# CUK_3Ph_Analog_Isolation.net
KiCad netlist of a schematic drawn in Altium Designer
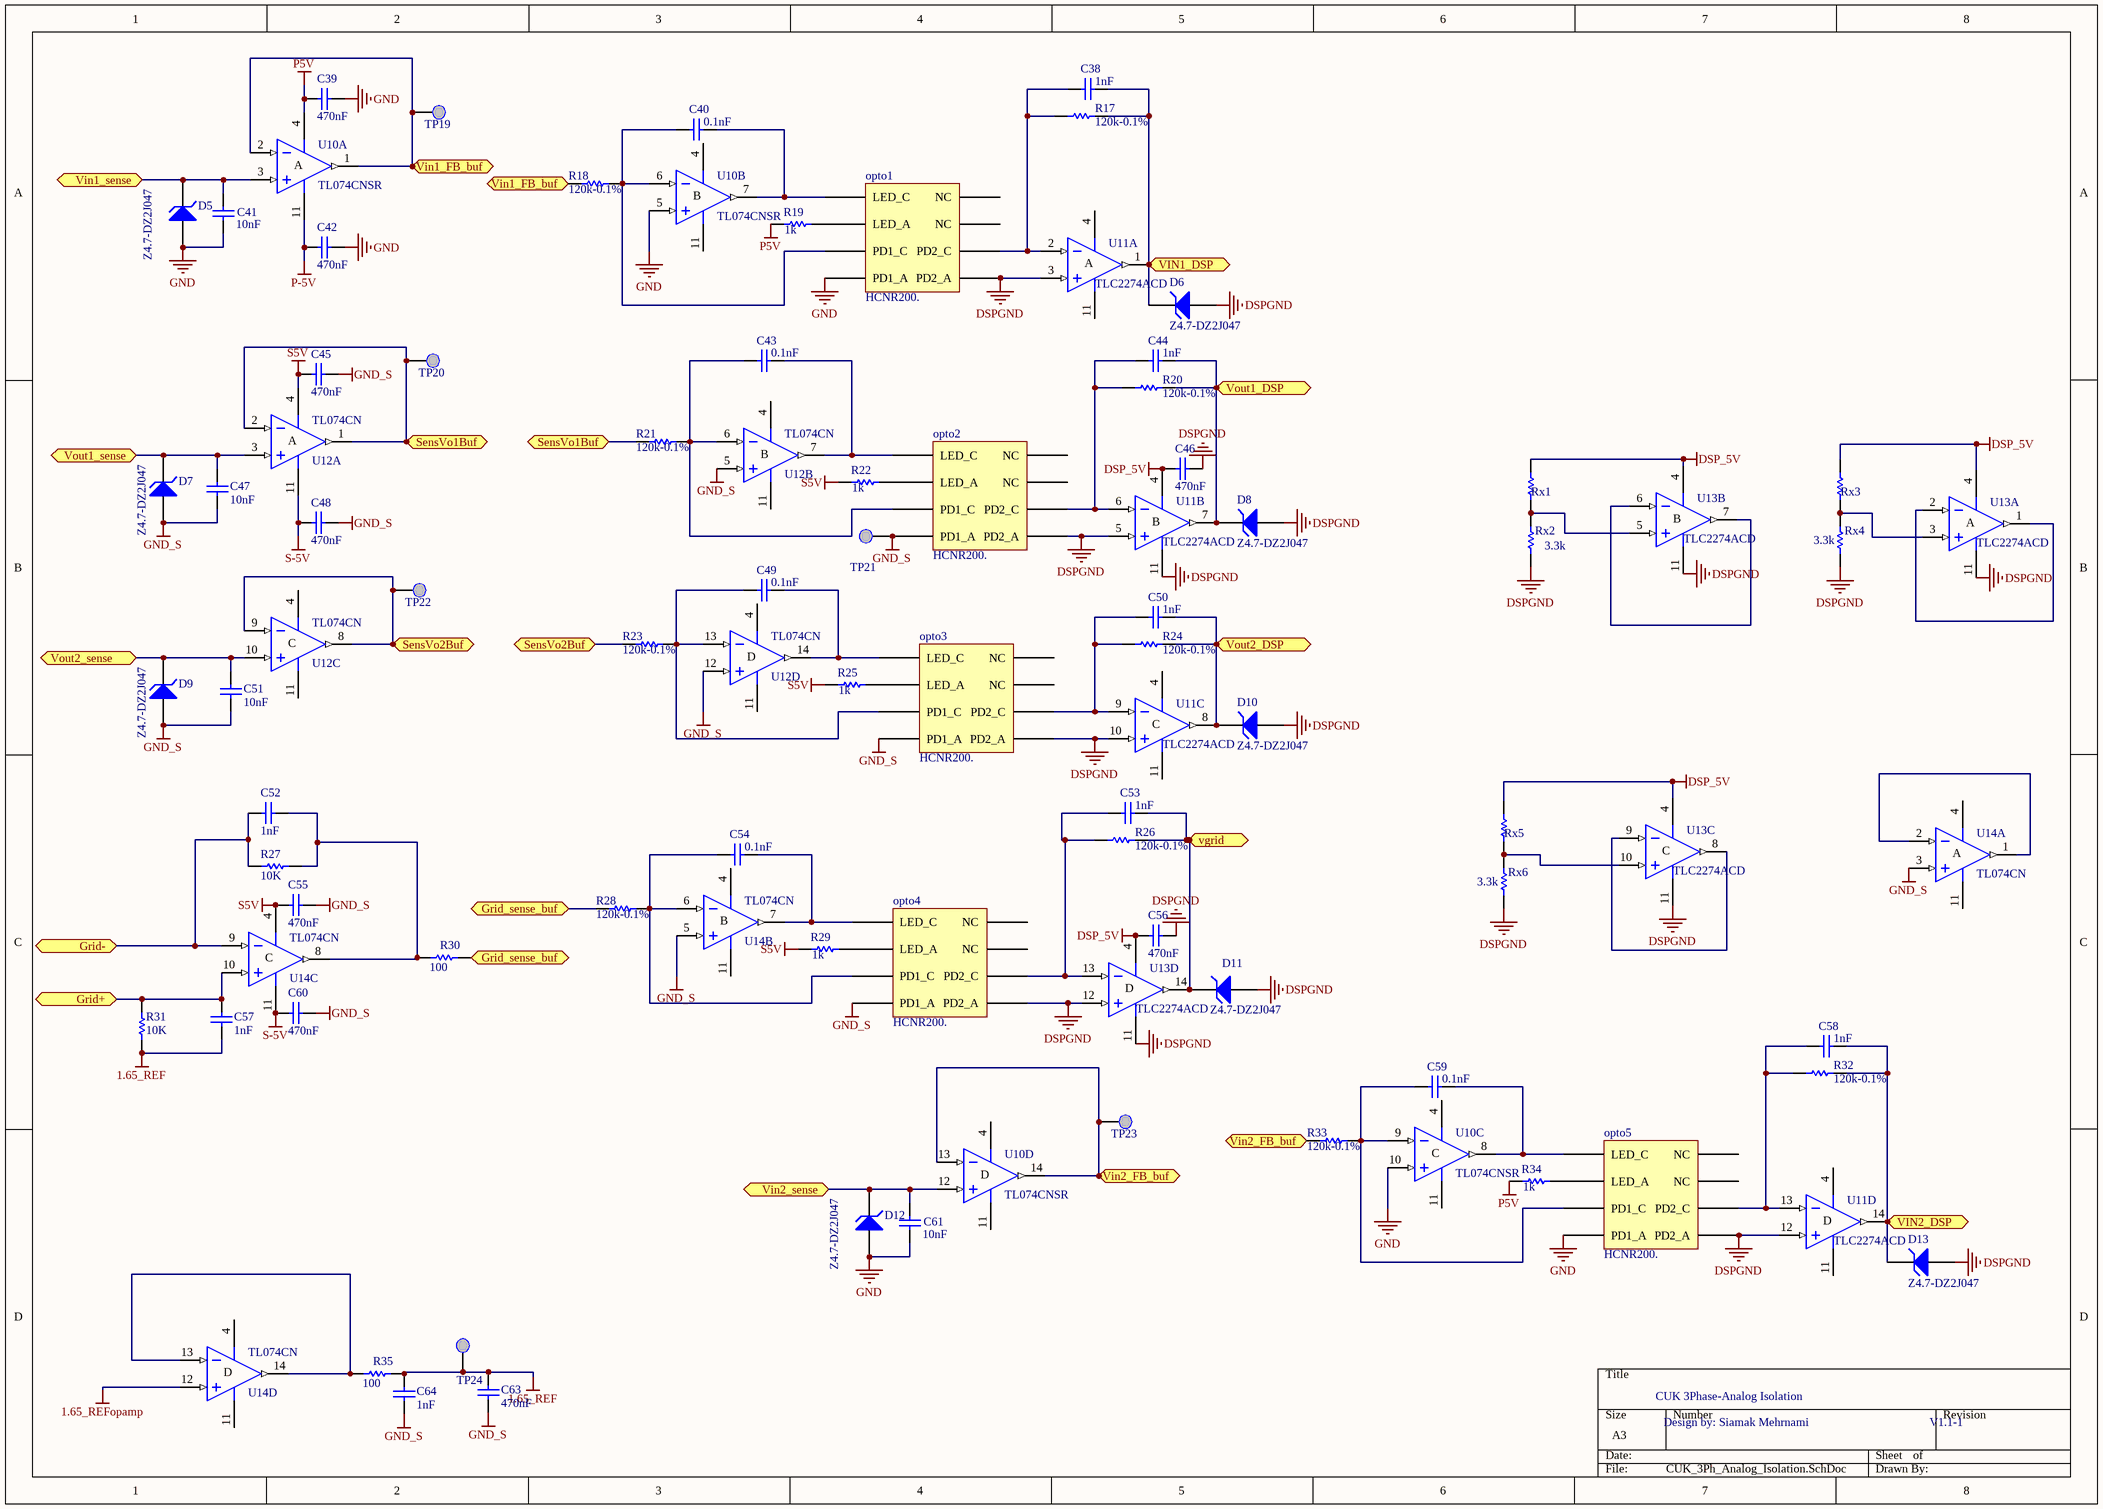
[diagram p0: CUK_3Ph_Analog_Isolation.SchDoc]

(export (version "E")
  (design (tool "Eeschema 10.0.6"))
  (components
    (comp (ref "C38")
      (value "1nF")
      (footprint "Capacitor 0805")
      (description "Capacitor")
      (fields (field (name "Comment") "Cap") (field (name "PUBLISHER") "Altium Limited"))
      (libsource (lib "Miscellaneous Devices") (part "Cap"))
    )
    (comp (ref "C39")
      (value "470nF")
      (footprint "Capacitor 0805")
      (description "Capacitor")
      (fields (field (name "Comment") "Cap") (field (name "PUBLISHER") "Altium Limited"))
      (libsource (lib "Miscellaneous Devices") (part "Cap"))
    )
    (comp (ref "C40")
      (value "0.1nF")
      (footprint "Capacitor 0805")
      (description "Capacitor")
      (fields (field (name "Comment") "Cap") (field (name "PUBLISHER") "Altium Limited"))
      (libsource (lib "Miscellaneous Devices") (part "Cap"))
    )
    (comp (ref "C41")
      (value "10nF")
      (footprint "Capacitor 0805")
      (description "Capacitor")
      (fields (field (name "Comment") "Cap") (field (name "PUBLISHER") "Altium Limited"))
      (libsource (lib "Miscellaneous Devices") (part "Cap"))
    )
    (comp (ref "C42")
      (value "470nF")
      (footprint "Capacitor 0805")
      (description "Capacitor")
      (fields (field (name "Comment") "Cap") (field (name "PUBLISHER") "Altium Limited"))
      (libsource (lib "Miscellaneous Devices") (part "Cap"))
    )
    (comp (ref "C43")
      (value "0.1nF")
      (footprint "Capacitor 0805")
      (description "Capacitor")
      (fields (field (name "Comment") "Cap") (field (name "PUBLISHER") "Altium Limited"))
      (libsource (lib "Miscellaneous Devices") (part "Cap"))
    )
    (comp (ref "C44")
      (value "1nF")
      (footprint "Capacitor 0805")
      (description "Capacitor")
      (fields (field (name "Comment") "Cap") (field (name "PUBLISHER") "Altium Limited"))
      (libsource (lib "Miscellaneous Devices") (part "Cap"))
    )
    (comp (ref "C45")
      (value "470nF")
      (footprint "Capacitor 0805")
      (description "Capacitor")
      (fields (field (name "Comment") "Cap") (field (name "PUBLISHER") "Altium Limited"))
      (libsource (lib "Miscellaneous Devices") (part "Cap"))
    )
    (comp (ref "C46")
      (value "470nF")
      (footprint "Capacitor 0805")
      (description "Capacitor")
      (fields (field (name "Comment") "Cap") (field (name "PUBLISHER") "Altium Limited"))
      (libsource (lib "Miscellaneous Devices") (part "Cap"))
    )
    (comp (ref "C47")
      (value "10nF")
      (footprint "Capacitor 0805")
      (description "Capacitor")
      (fields (field (name "Comment") "Cap") (field (name "PUBLISHER") "Altium Limited"))
      (libsource (lib "Miscellaneous Devices") (part "Cap"))
    )
    (comp (ref "C48")
      (value "470nF")
      (footprint "Capacitor 0805")
      (description "Capacitor")
      (fields (field (name "Comment") "Cap") (field (name "PUBLISHER") "Altium Limited"))
      (libsource (lib "Miscellaneous Devices") (part "Cap"))
    )
    (comp (ref "C49")
      (value "0.1nF")
      (footprint "Capacitor 0805")
      (description "Capacitor")
      (fields (field (name "Comment") "Cap") (field (name "PUBLISHER") "Altium Limited"))
      (libsource (lib "Miscellaneous Devices") (part "Cap"))
    )
    (comp (ref "C50")
      (value "1nF")
      (footprint "Capacitor 0805")
      (description "Capacitor")
      (fields (field (name "Comment") "Cap") (field (name "PUBLISHER") "Altium Limited"))
      (libsource (lib "Miscellaneous Devices") (part "Cap"))
    )
    (comp (ref "C51")
      (value "10nF")
      (footprint "Capacitor 0805")
      (description "Capacitor")
      (fields (field (name "Comment") "Cap") (field (name "PUBLISHER") "Altium Limited"))
      (libsource (lib "Miscellaneous Devices") (part "Cap"))
    )
    (comp (ref "C52")
      (value "1nF")
      (footprint "Capacitor 0805")
      (description "Capacitor")
      (fields (field (name "Comment") "Cap") (field (name "PUBLISHER") "Altium Limited"))
      (libsource (lib "Miscellaneous Devices") (part "Cap"))
    )
    (comp (ref "C53")
      (value "1nF")
      (footprint "Capacitor 0805")
      (description "Capacitor")
      (fields (field (name "Comment") "Cap") (field (name "PUBLISHER") "Altium Limited"))
      (libsource (lib "Miscellaneous Devices") (part "Cap"))
    )
    (comp (ref "C54")
      (value "0.1nF")
      (footprint "Capacitor 0805")
      (description "Capacitor")
      (fields (field (name "Comment") "Cap") (field (name "PUBLISHER") "Altium Limited"))
      (libsource (lib "Miscellaneous Devices") (part "Cap"))
    )
    (comp (ref "C55")
      (value "470nF")
      (footprint "Capacitor 0805")
      (description "Capacitor")
      (fields (field (name "Comment") "Cap") (field (name "PUBLISHER") "Altium Limited"))
      (libsource (lib "Miscellaneous Devices") (part "Cap"))
    )
    (comp (ref "C56")
      (value "470nF")
      (footprint "Capacitor 0805")
      (description "Capacitor")
      (fields (field (name "Comment") "Cap") (field (name "PUBLISHER") "Altium Limited"))
      (libsource (lib "Miscellaneous Devices") (part "Cap"))
    )
    (comp (ref "C57")
      (value "1nF")
      (footprint "Capacitor 0805")
      (description "Capacitor")
      (fields (field (name "Comment") "Cap") (field (name "PUBLISHER") "Altium Limited"))
      (libsource (lib "Miscellaneous Devices") (part "Cap"))
    )
    (comp (ref "C58")
      (value "1nF")
      (footprint "Capacitor 0805")
      (description "Capacitor")
      (fields (field (name "Comment") "Cap") (field (name "PUBLISHER") "Altium Limited"))
      (libsource (lib "Miscellaneous Devices") (part "Cap"))
    )
    (comp (ref "C59")
      (value "0.1nF")
      (footprint "Capacitor 0805")
      (description "Capacitor")
      (fields (field (name "Comment") "Cap") (field (name "PUBLISHER") "Altium Limited"))
      (libsource (lib "Miscellaneous Devices") (part "Cap"))
    )
    (comp (ref "C60")
      (value "470nF")
      (footprint "Capacitor 0805")
      (description "Capacitor")
      (fields (field (name "Comment") "Cap") (field (name "PUBLISHER") "Altium Limited"))
      (libsource (lib "Miscellaneous Devices") (part "Cap"))
    )
    (comp (ref "C61")
      (value "10nF")
      (footprint "Capacitor 0805")
      (description "Capacitor")
      (fields (field (name "Comment") "Cap") (field (name "PUBLISHER") "Altium Limited"))
      (libsource (lib "Miscellaneous Devices") (part "Cap"))
    )
    (comp (ref "C63")
      (value "470nF")
      (footprint "Capacitor 0805")
      (description "Capacitor")
      (fields (field (name "Comment") "Cap") (field (name "PUBLISHER") "Altium Limited"))
      (libsource (lib "Miscellaneous Devices") (part "Cap"))
    )
    (comp (ref "C64")
      (value "1nF")
      (footprint "Capacitor 0805")
      (description "Capacitor")
      (fields (field (name "Comment") "Cap") (field (name "PUBLISHER") "Altium Limited"))
      (libsource (lib "Miscellaneous Devices") (part "Cap"))
    )
    (comp (ref "D5")
      (value "Z4.7-DZ2J047")
      (footprint "Zener DZ2J047")
      (description "Zener Diode")
      (fields (field (name "PUBLISHER") "Altium Limited"))
      (libsource (lib "Miscellaneous Devices") (part "D Zener"))
    )
    (comp (ref "D6")
      (value "Z4.7-DZ2J047")
      (footprint "Zener DZ2J047")
      (description "Zener Diode")
      (fields (field (name "PUBLISHER") "Altium Limited"))
      (libsource (lib "Miscellaneous Devices") (part "D Zener"))
    )
    (comp (ref "D7")
      (value "Z4.7-DZ2J047")
      (footprint "Zener DZ2J047")
      (description "Zener Diode")
      (fields (field (name "PUBLISHER") "Altium Limited"))
      (libsource (lib "Miscellaneous Devices") (part "D Zener"))
    )
    (comp (ref "D8")
      (value "Z4.7-DZ2J047")
      (footprint "Zener DZ2J047")
      (description "Zener Diode")
      (fields (field (name "PUBLISHER") "Altium Limited"))
      (libsource (lib "Miscellaneous Devices") (part "D Zener"))
    )
    (comp (ref "D9")
      (value "Z4.7-DZ2J047")
      (footprint "Zener DZ2J047")
      (description "Zener Diode")
      (fields (field (name "PUBLISHER") "Altium Limited"))
      (libsource (lib "Miscellaneous Devices") (part "D Zener"))
    )
    (comp (ref "D10")
      (value "Z4.7-DZ2J047")
      (footprint "Zener DZ2J047")
      (description "Zener Diode")
      (fields (field (name "PUBLISHER") "Altium Limited"))
      (libsource (lib "Miscellaneous Devices") (part "D Zener"))
    )
    (comp (ref "D11")
      (value "Z4.7-DZ2J047")
      (footprint "Zener DZ2J047")
      (description "Zener Diode")
      (fields (field (name "PUBLISHER") "Altium Limited"))
      (libsource (lib "Miscellaneous Devices") (part "D Zener"))
    )
    (comp (ref "D12")
      (value "Z4.7-DZ2J047")
      (footprint "Zener DZ2J047")
      (description "Zener Diode")
      (fields (field (name "PUBLISHER") "Altium Limited"))
      (libsource (lib "Miscellaneous Devices") (part "D Zener"))
    )
    (comp (ref "D13")
      (value "Z4.7-DZ2J047")
      (footprint "Zener DZ2J047")
      (description "Zener Diode")
      (fields (field (name "PUBLISHER") "Altium Limited"))
      (libsource (lib "Miscellaneous Devices") (part "D Zener"))
    )
    (comp (ref "opto1")
      (value "HCNR200.")
      (footprint "HCNR200")
      (libsource (lib "HCRN200") (part "Component_1"))
    )
    (comp (ref "opto2")
      (value "HCNR200.")
      (footprint "HCNR200")
      (libsource (lib "HCRN200") (part "Component_1"))
    )
    (comp (ref "opto3")
      (value "HCNR200.")
      (footprint "HCNR200")
      (libsource (lib "HCRN200") (part "Component_1"))
    )
    (comp (ref "opto4")
      (value "HCNR200.")
      (footprint "HCNR200")
      (libsource (lib "HCRN200") (part "Component_1"))
    )
    (comp (ref "opto5")
      (value "HCNR200.")
      (footprint "HCNR200")
      (libsource (lib "HCRN200") (part "Component_1"))
    )
    (comp (ref "R17")
      (value "120k-0.1%")
      (footprint "0805 RES")
      (description "Resistor")
      (fields (field (name "Comment") "Res1") (field (name "PUBLISHER") "Altium Limited"))
      (libsource (lib "Miscellaneous Devices") (part "Res1"))
    )
    (comp (ref "R18")
      (value "120k-0.1%")
      (footprint "0805 RES")
      (description "Resistor")
      (fields (field (name "Comment") "Res1") (field (name "PUBLISHER") "Altium Limited"))
      (libsource (lib "Miscellaneous Devices") (part "Res1"))
    )
    (comp (ref "R19")
      (value "1k")
      (footprint "0805 RES")
      (description "Resistor")
      (fields (field (name "Comment") "Res1") (field (name "PUBLISHER") "Altium Limited"))
      (libsource (lib "Miscellaneous Devices") (part "Res1"))
    )
    (comp (ref "R20")
      (value "120k-0.1%")
      (footprint "0805 RES")
      (description "Resistor")
      (fields (field (name "Comment") "Res1") (field (name "PUBLISHER") "Altium Limited"))
      (libsource (lib "Miscellaneous Devices") (part "Res1"))
    )
    (comp (ref "R21")
      (value "120k-0.1%")
      (footprint "0805 RES")
      (description "Resistor")
      (fields (field (name "Comment") "Res1") (field (name "PUBLISHER") "Altium Limited"))
      (libsource (lib "Miscellaneous Devices") (part "Res1"))
    )
    (comp (ref "R22")
      (value "1k")
      (footprint "0805 RES")
      (description "Resistor")
      (fields (field (name "Comment") "Res1") (field (name "PUBLISHER") "Altium Limited"))
      (libsource (lib "Miscellaneous Devices") (part "Res1"))
    )
    (comp (ref "R23")
      (value "120k-0.1%")
      (footprint "0805 RES")
      (description "Resistor")
      (fields (field (name "Comment") "Res1") (field (name "PUBLISHER") "Altium Limited"))
      (libsource (lib "Miscellaneous Devices") (part "Res1"))
    )
    (comp (ref "R24")
      (value "120k-0.1%")
      (footprint "0805 RES")
      (description "Resistor")
      (fields (field (name "Comment") "Res1") (field (name "PUBLISHER") "Altium Limited"))
      (libsource (lib "Miscellaneous Devices") (part "Res1"))
    )
    (comp (ref "R25")
      (value "1k")
      (footprint "0805 RES")
      (description "Resistor")
      (fields (field (name "Comment") "Res1") (field (name "PUBLISHER") "Altium Limited"))
      (libsource (lib "Miscellaneous Devices") (part "Res1"))
    )
    (comp (ref "R26")
      (value "120k-0.1%")
      (footprint "0805 RES")
      (description "Resistor")
      (fields (field (name "Comment") "Res1") (field (name "PUBLISHER") "Altium Limited"))
      (libsource (lib "Miscellaneous Devices") (part "Res1"))
    )
    (comp (ref "R27")
      (value "10K")
      (footprint "0805 RES")
      (description "Resistor")
      (fields (field (name "Comment") "Res1") (field (name "PUBLISHER") "Altium Limited"))
      (libsource (lib "Miscellaneous Devices") (part "Res1"))
    )
    (comp (ref "R28")
      (value "120k-0.1%")
      (footprint "0805 RES")
      (description "Resistor")
      (fields (field (name "Comment") "Res1") (field (name "PUBLISHER") "Altium Limited"))
      (libsource (lib "Miscellaneous Devices") (part "Res1"))
    )
    (comp (ref "R29")
      (value "1k")
      (footprint "0805 RES")
      (description "Resistor")
      (fields (field (name "Comment") "Res1") (field (name "PUBLISHER") "Altium Limited"))
      (libsource (lib "Miscellaneous Devices") (part "Res1"))
    )
    (comp (ref "R30")
      (value "100")
      (footprint "0805 RES")
      (description "Resistor")
      (fields (field (name "Comment") "Res1") (field (name "PUBLISHER") "Altium Limited"))
      (libsource (lib "Miscellaneous Devices") (part "Res1"))
    )
    (comp (ref "R31")
      (value "10K")
      (footprint "0805 RES")
      (description "Resistor")
      (fields (field (name "Comment") "Res1") (field (name "PUBLISHER") "Altium Limited"))
      (libsource (lib "Miscellaneous Devices") (part "Res1"))
    )
    (comp (ref "R32")
      (value "120k-0.1%")
      (footprint "0805 RES")
      (description "Resistor")
      (fields (field (name "Comment") "Res1") (field (name "PUBLISHER") "Altium Limited"))
      (libsource (lib "Miscellaneous Devices") (part "Res1"))
    )
    (comp (ref "R33")
      (value "120k-0.1%")
      (footprint "0805 RES")
      (description "Resistor")
      (fields (field (name "Comment") "Res1") (field (name "PUBLISHER") "Altium Limited"))
      (libsource (lib "Miscellaneous Devices") (part "Res1"))
    )
    (comp (ref "R34")
      (value "1k")
      (footprint "0805 RES")
      (description "Resistor")
      (fields (field (name "Comment") "Res1") (field (name "PUBLISHER") "Altium Limited"))
      (libsource (lib "Miscellaneous Devices") (part "Res1"))
    )
    (comp (ref "R35")
      (value "100")
      (footprint "0805 RES")
      (description "Resistor")
      (fields (field (name "Comment") "Res1") (field (name "PUBLISHER") "Altium Limited"))
      (libsource (lib "Miscellaneous Devices") (part "Res1"))
    )
    (comp (ref "Rx1")
      (value "Res1")
      (footprint "0805 RES")
      (description "Resistor")
      (fields (field (name "PUBLISHER") "Altium Limited"))
      (libsource (lib "control Board") (part "Res1"))
    )
    (comp (ref "Rx2")
      (value "3.3k")
      (footprint "0805 RES")
      (description "Resistor")
      (fields (field (name "Comment") "Res1") (field (name "PUBLISHER") "Altium Limited"))
      (libsource (lib "control Board") (part "Res1"))
    )
    (comp (ref "Rx3")
      (value "Res1")
      (footprint "0805 RES")
      (description "Resistor")
      (fields (field (name "PUBLISHER") "Altium Limited"))
      (libsource (lib "control Board") (part "Res1"))
    )
    (comp (ref "Rx4")
      (value "3.3k")
      (footprint "0805 RES")
      (description "Resistor")
      (fields (field (name "Comment") "Res1") (field (name "PUBLISHER") "Altium Limited"))
      (libsource (lib "control Board") (part "Res1"))
    )
    (comp (ref "Rx5")
      (value "Res1")
      (footprint "0805 RES")
      (description "Resistor")
      (fields (field (name "PUBLISHER") "Altium Limited"))
      (libsource (lib "control Board") (part "Res1"))
    )
    (comp (ref "Rx6")
      (value "3.3k")
      (footprint "0805 RES")
      (description "Resistor")
      (fields (field (name "Comment") "Res1") (field (name "PUBLISHER") "Altium Limited"))
      (libsource (lib "control Board") (part "Res1"))
    )
    (comp (ref "TP19")
      (value "Test point")
      (footprint "Test Point")
      (libsource (lib "CUK1") (part "Test point"))
    )
    (comp (ref "TP20")
      (value "Test point")
      (footprint "Test Point")
      (libsource (lib "CUK1") (part "Test point"))
    )
    (comp (ref "TP21")
      (value "Test point")
      (footprint "Test Point")
      (libsource (lib "CUK1") (part "Test point"))
    )
    (comp (ref "TP22")
      (value "Test point")
      (footprint "Test Point")
      (libsource (lib "CUK1") (part "Test point"))
    )
    (comp (ref "TP23")
      (value "Test point")
      (footprint "Test Point")
      (libsource (lib "CUK1") (part "Test point"))
    )
    (comp (ref "TP24")
      (value "Test point")
      (footprint "Test Point")
      (libsource (lib "control Board") (part "Test point"))
    )
    (comp (ref "U10")
      (value "TL074CNSR")
      (footprint "DIP14")
      (description "Low-Noise JFET-Input Operational Amplifier")
      (fields (field (name "PUBLISHER") "Altium Limited"))
      (libsource (lib "TI Operational Amplifier") (part "TL074J"))
    )
    (comp (ref "U11")
      (value "TLC2274ACD")
      (footprint "SOIC14")
      (description "Very Low-Power CMOS Quad Operational Amplifier")
      (fields (field (name "PUBLISHER") "Altium Limited"))
      (libsource (lib "ST Operational Amplifier") (part "TS27L4AMD"))
    )
    (comp (ref "U12")
      (value "TL074CN")
      (footprint "DIP14")
      (description "Low-Noise JFET-Input Operational Amplifier")
      (fields (field (name "PUBLISHER") "Altium Limited"))
      (libsource (lib "TI Operational Amplifier") (part "TL074J"))
    )
    (comp (ref "U13")
      (value "TLC2274ACD")
      (footprint "SOIC14")
      (description "Very Low-Power CMOS Quad Operational Amplifier")
      (fields (field (name "PUBLISHER") "Altium Limited"))
      (libsource (lib "ST Operational Amplifier") (part "TS27L4AMD"))
    )
    (comp (ref "U14")
      (value "TL074CN")
      (footprint "DIP14")
      (description "Low-Noise JFET-Input Operational Amplifier")
      (fields (field (name "PUBLISHER") "Altium Limited"))
      (libsource (lib "TI Operational Amplifier") (part "TL074J"))
    )
  )
  (nets
    (net (code "1") (name "/Grid+") (class "Default")
      (node (ref "C57") (pin "1") (pinfunction "1_1") (pintype "passive"))
      (node (ref "R31") (pin "2") (pinfunction "2_2") (pintype "passive"))
      (node (ref "U14") (pin "10") (pinfunction "IN+_10") (pintype "input"))
    )
    (net (code "2") (name "/Grid-") (class "Default")
      (node (ref "C52") (pin "1") (pinfunction "1_1") (pintype "passive"))
      (node (ref "R27") (pin "2") (pinfunction "2_2") (pintype "passive"))
      (node (ref "U14") (pin "9") (pinfunction "IN-_9") (pintype "input"))
    )
    (net (code "3") (name "/Grid_sense_buf") (class "Default")
      (node (ref "R28") (pin "1") (pinfunction "1_1") (pintype "passive"))
      (node (ref "R30") (pin "1") (pinfunction "1_1") (pintype "passive"))
    )
    (net (code "4") (name "/SensVo1Buf") (class "Default")
      (node (ref "R21") (pin "1") (pinfunction "1_1") (pintype "passive"))
      (node (ref "TP20") (pin "1") (pintype "passive"))
      (node (ref "U12") (pin "1") (pinfunction "OUT_1") (pintype "output"))
      (node (ref "U12") (pin "2") (pinfunction "IN-_2") (pintype "input"))
    )
    (net (code "5") (name "/SensVo2Buf") (class "Default")
      (node (ref "R23") (pin "1") (pinfunction "1_1") (pintype "passive"))
      (node (ref "TP22") (pin "1") (pintype "passive"))
      (node (ref "U12") (pin "8") (pinfunction "OUT_8") (pintype "output"))
      (node (ref "U12") (pin "9") (pinfunction "IN-_9") (pintype "input"))
    )
    (net (code "6") (name "/VIN1_DSP") (class "Default")
      (node (ref "C38") (pin "2") (pinfunction "2_2") (pintype "passive"))
      (node (ref "D6") (pin "2") (pinfunction "K_2") (pintype "passive"))
      (node (ref "R17") (pin "2") (pinfunction "2_2") (pintype "passive"))
      (node (ref "U11") (pin "1") (pinfunction "OUT_1") (pintype "output"))
    )
    (net (code "7") (name "/VIN2_DSP") (class "Default")
      (node (ref "C58") (pin "2") (pinfunction "2_2") (pintype "passive"))
      (node (ref "D13") (pin "2") (pinfunction "K_2") (pintype "passive"))
      (node (ref "R32") (pin "2") (pinfunction "2_2") (pintype "passive"))
      (node (ref "U11") (pin "14") (pinfunction "OUT_14") (pintype "output"))
    )
    (net (code "8") (name "/Vin1_FB_buf") (class "Default")
      (node (ref "R18") (pin "1") (pinfunction "1_1") (pintype "passive"))
      (node (ref "TP19") (pin "1") (pintype "passive"))
      (node (ref "U10") (pin "1") (pinfunction "OUT_1") (pintype "output"))
      (node (ref "U10") (pin "2") (pinfunction "IN-_2") (pintype "input"))
    )
    (net (code "9") (name "/Vin1_sense") (class "Default")
      (node (ref "C41") (pin "1") (pinfunction "1_1") (pintype "passive"))
      (node (ref "D5") (pin "2") (pinfunction "K_2") (pintype "passive"))
      (node (ref "U10") (pin "3") (pinfunction "IN+_3") (pintype "input"))
    )
    (net (code "10") (name "/Vin2_FB_buf") (class "Default")
      (node (ref "R33") (pin "1") (pinfunction "1_1") (pintype "passive"))
      (node (ref "TP23") (pin "1") (pintype "passive"))
      (node (ref "U10") (pin "13") (pinfunction "IN-_13") (pintype "input"))
      (node (ref "U10") (pin "14") (pinfunction "OUT_14") (pintype "output"))
    )
    (net (code "11") (name "/Vin2_sense") (class "Default")
      (node (ref "C61") (pin "1") (pinfunction "1_1") (pintype "passive"))
      (node (ref "D12") (pin "2") (pinfunction "K_2") (pintype "passive"))
      (node (ref "U10") (pin "12") (pinfunction "IN+_12") (pintype "input"))
    )
    (net (code "12") (name "/Vout1_DSP") (class "Default")
      (node (ref "C44") (pin "2") (pinfunction "2_2") (pintype "passive"))
      (node (ref "D8") (pin "2") (pinfunction "K_2") (pintype "passive"))
      (node (ref "R20") (pin "2") (pinfunction "2_2") (pintype "passive"))
      (node (ref "U11") (pin "7") (pinfunction "OUT_7") (pintype "output"))
    )
    (net (code "13") (name "/Vout1_sense") (class "Default")
      (node (ref "C47") (pin "1") (pinfunction "1_1") (pintype "passive"))
      (node (ref "D7") (pin "2") (pinfunction "K_2") (pintype "passive"))
      (node (ref "U12") (pin "3") (pinfunction "IN+_3") (pintype "input"))
    )
    (net (code "14") (name "/Vout2_DSP") (class "Default")
      (node (ref "C50") (pin "2") (pinfunction "2_2") (pintype "passive"))
      (node (ref "D10") (pin "2") (pinfunction "K_2") (pintype "passive"))
      (node (ref "R24") (pin "2") (pinfunction "2_2") (pintype "passive"))
      (node (ref "U11") (pin "8") (pinfunction "OUT_8") (pintype "output"))
    )
    (net (code "15") (name "/Vout2_sense") (class "Default")
      (node (ref "C51") (pin "1") (pinfunction "1_1") (pintype "passive"))
      (node (ref "D9") (pin "2") (pinfunction "K_2") (pintype "passive"))
      (node (ref "U12") (pin "10") (pinfunction "IN+_10") (pintype "input"))
    )
    (net (code "16") (name "/vgrid") (class "Default")
      (node (ref "C53") (pin "2") (pinfunction "2_2") (pintype "passive"))
      (node (ref "D11") (pin "2") (pinfunction "K_2") (pintype "passive"))
      (node (ref "R26") (pin "2") (pinfunction "2_2") (pintype "passive"))
      (node (ref "U13") (pin "14") (pinfunction "OUT_14") (pintype "output"))
    )
    (net (code "17") (name "1.65_REF") (class "Default")
      (node (ref "C57") (pin "2") (pinfunction "2_2") (pintype "passive"))
      (node (ref "C63") (pin "1") (pinfunction "1_1") (pintype "passive"))
      (node (ref "C64") (pin "1") (pinfunction "1_1") (pintype "passive"))
      (node (ref "R31") (pin "1") (pinfunction "1_1") (pintype "passive"))
      (node (ref "R35") (pin "1") (pinfunction "1_1") (pintype "passive"))
      (node (ref "TP24") (pin "1") (pintype "passive"))
    )
    (net (code "18") (name "1.65_REFopamp") (class "Default")
      (node (ref "U14") (pin "12") (pinfunction "IN+_12") (pintype "input"))
    )
    (net (code "19") (name "DSPGND") (class "Default")
      (node (ref "C46") (pin "1") (pinfunction "1_1") (pintype "passive"))
      (node (ref "C56") (pin "1") (pinfunction "1_1") (pintype "passive"))
      (node (ref "D10") (pin "1") (pinfunction "A_1") (pintype "passive"))
      (node (ref "D11") (pin "1") (pinfunction "A_1") (pintype "passive"))
      (node (ref "D13") (pin "1") (pinfunction "A_1") (pintype "passive"))
      (node (ref "D6") (pin "1") (pinfunction "A_1") (pintype "passive"))
      (node (ref "D8") (pin "1") (pinfunction "A_1") (pintype "passive"))
      (node (ref "Rx2") (pin "1") (pinfunction "1_1") (pintype "passive"))
      (node (ref "Rx4") (pin "1") (pinfunction "1_1") (pintype "passive"))
      (node (ref "Rx6") (pin "1") (pinfunction "1_1") (pintype "passive"))
      (node (ref "U11") (pin "10") (pinfunction "IN+_10") (pintype "input"))
      (node (ref "U11") (pin "11") (pinfunction "V-_11") (pintype "power_in"))
      (node (ref "U11") (pin "12") (pinfunction "IN+_12") (pintype "input"))
      (node (ref "U11") (pin "3") (pinfunction "IN+_3") (pintype "input"))
      (node (ref "U11") (pin "5") (pinfunction "IN+_5") (pintype "input"))
      (node (ref "U13") (pin "11") (pinfunction "V-_11") (pintype "power_in"))
      (node (ref "U13") (pin "12") (pinfunction "IN+_12") (pintype "input"))
      (node (ref "opto1") (pin "5") (pinfunction "PD2_A_5") (pintype "passive"))
      (node (ref "opto2") (pin "5") (pinfunction "PD2_A_5") (pintype "passive"))
      (node (ref "opto3") (pin "5") (pinfunction "PD2_A_5") (pintype "passive"))
      (node (ref "opto4") (pin "5") (pinfunction "PD2_A_5") (pintype "passive"))
      (node (ref "opto5") (pin "5") (pinfunction "PD2_A_5") (pintype "passive"))
    )
    (net (code "20") (name "DSP_5V") (class "Default")
      (node (ref "C46") (pin "2") (pinfunction "2_2") (pintype "passive"))
      (node (ref "C56") (pin "2") (pinfunction "2_2") (pintype "passive"))
      (node (ref "Rx1") (pin "2") (pinfunction "2_2") (pintype "passive"))
      (node (ref "Rx3") (pin "2") (pinfunction "2_2") (pintype "passive"))
      (node (ref "Rx5") (pin "2") (pinfunction "2_2") (pintype "passive"))
      (node (ref "U11") (pin "4") (pinfunction "V+_4") (pintype "power_in"))
      (node (ref "U13") (pin "4") (pinfunction "V+_4") (pintype "power_in"))
    )
    (net (code "21") (name "GND") (class "Default")
      (node (ref "C39") (pin "1") (pinfunction "1_1") (pintype "passive"))
      (node (ref "C41") (pin "2") (pinfunction "2_2") (pintype "passive"))
      (node (ref "C42") (pin "1") (pinfunction "1_1") (pintype "passive"))
      (node (ref "C61") (pin "2") (pinfunction "2_2") (pintype "passive"))
      (node (ref "D12") (pin "1") (pinfunction "A_1") (pintype "passive"))
      (node (ref "D5") (pin "1") (pinfunction "A_1") (pintype "passive"))
      (node (ref "U10") (pin "10") (pinfunction "IN+_10") (pintype "input"))
      (node (ref "U10") (pin "5") (pinfunction "IN+_5") (pintype "input"))
      (node (ref "opto1") (pin "4") (pinfunction "PD1_A_4") (pintype "passive"))
      (node (ref "opto5") (pin "4") (pinfunction "PD1_A_4") (pintype "passive"))
    )
    (net (code "22") (name "GND_S") (class "Default")
      (node (ref "C45") (pin "1") (pinfunction "1_1") (pintype "passive"))
      (node (ref "C47") (pin "2") (pinfunction "2_2") (pintype "passive"))
      (node (ref "C48") (pin "1") (pinfunction "1_1") (pintype "passive"))
      (node (ref "C51") (pin "2") (pinfunction "2_2") (pintype "passive"))
      (node (ref "C55") (pin "1") (pinfunction "1_1") (pintype "passive"))
      (node (ref "C60") (pin "1") (pinfunction "1_1") (pintype "passive"))
      (node (ref "C63") (pin "2") (pinfunction "2_2") (pintype "passive"))
      (node (ref "C64") (pin "2") (pinfunction "2_2") (pintype "passive"))
      (node (ref "D7") (pin "1") (pinfunction "A_1") (pintype "passive"))
      (node (ref "D9") (pin "1") (pinfunction "A_1") (pintype "passive"))
      (node (ref "TP21") (pin "1") (pintype "passive"))
      (node (ref "U12") (pin "12") (pinfunction "IN+_12") (pintype "input"))
      (node (ref "U12") (pin "5") (pinfunction "IN+_5") (pintype "input"))
      (node (ref "U14") (pin "3") (pinfunction "IN+_3") (pintype "input"))
      (node (ref "U14") (pin "5") (pinfunction "IN+_5") (pintype "input"))
      (node (ref "opto2") (pin "4") (pinfunction "PD1_A_4") (pintype "passive"))
      (node (ref "opto3") (pin "4") (pinfunction "PD1_A_4") (pintype "passive"))
      (node (ref "opto4") (pin "4") (pinfunction "PD1_A_4") (pintype "passive"))
    )
    (net (code "23") (name "Net-(U10B-IN-)") (class "Default")
      (node (ref "C40") (pin "1") (pinfunction "1_1") (pintype "passive"))
      (node (ref "R18") (pin "2") (pinfunction "2_2") (pintype "passive"))
      (node (ref "U10") (pin "6") (pinfunction "IN-_6") (pintype "input"))
      (node (ref "opto1") (pin "3") (pinfunction "PD1_C_3") (pintype "passive"))
    )
    (net (code "24") (name "Net-(U10B-OUT)") (class "Default")
      (node (ref "C40") (pin "2") (pinfunction "2_2") (pintype "passive"))
      (node (ref "U10") (pin "7") (pinfunction "OUT_7") (pintype "output"))
      (node (ref "opto1") (pin "1") (pinfunction "LED_C_1") (pintype "passive"))
    )
    (net (code "25") (name "Net-(U10C-IN-)") (class "Default")
      (node (ref "C59") (pin "1") (pinfunction "1_1") (pintype "passive"))
      (node (ref "R33") (pin "2") (pinfunction "2_2") (pintype "passive"))
      (node (ref "U10") (pin "9") (pinfunction "IN-_9") (pintype "input"))
      (node (ref "opto5") (pin "3") (pinfunction "PD1_C_3") (pintype "passive"))
    )
    (net (code "26") (name "Net-(U10C-OUT)") (class "Default")
      (node (ref "C59") (pin "2") (pinfunction "2_2") (pintype "passive"))
      (node (ref "U10") (pin "8") (pinfunction "OUT_8") (pintype "output"))
      (node (ref "opto5") (pin "1") (pinfunction "LED_C_1") (pintype "passive"))
    )
    (net (code "27") (name "Net-(U11A-IN-)") (class "Default")
      (node (ref "C38") (pin "1") (pinfunction "1_1") (pintype "passive"))
      (node (ref "R17") (pin "1") (pinfunction "1_1") (pintype "passive"))
      (node (ref "U11") (pin "2") (pinfunction "IN-_2") (pintype "input"))
      (node (ref "opto1") (pin "6") (pinfunction "PD2_C_6") (pintype "passive"))
    )
    (net (code "28") (name "Net-(U11B-IN-)") (class "Default")
      (node (ref "C44") (pin "1") (pinfunction "1_1") (pintype "passive"))
      (node (ref "R20") (pin "1") (pinfunction "1_1") (pintype "passive"))
      (node (ref "U11") (pin "6") (pinfunction "IN-_6") (pintype "input"))
      (node (ref "opto2") (pin "6") (pinfunction "PD2_C_6") (pintype "passive"))
    )
    (net (code "29") (name "Net-(U11C-IN-)") (class "Default")
      (node (ref "C50") (pin "1") (pinfunction "1_1") (pintype "passive"))
      (node (ref "R24") (pin "1") (pinfunction "1_1") (pintype "passive"))
      (node (ref "U11") (pin "9") (pinfunction "IN-_9") (pintype "input"))
      (node (ref "opto3") (pin "6") (pinfunction "PD2_C_6") (pintype "passive"))
    )
    (net (code "30") (name "Net-(U11D-IN-)") (class "Default")
      (node (ref "C58") (pin "1") (pinfunction "1_1") (pintype "passive"))
      (node (ref "R32") (pin "1") (pinfunction "1_1") (pintype "passive"))
      (node (ref "U11") (pin "13") (pinfunction "IN-_13") (pintype "input"))
      (node (ref "opto5") (pin "6") (pinfunction "PD2_C_6") (pintype "passive"))
    )
    (net (code "31") (name "Net-(U12B-IN-)") (class "Default")
      (node (ref "C43") (pin "1") (pinfunction "1_1") (pintype "passive"))
      (node (ref "R21") (pin "2") (pinfunction "2_2") (pintype "passive"))
      (node (ref "U12") (pin "6") (pinfunction "IN-_6") (pintype "input"))
      (node (ref "opto2") (pin "3") (pinfunction "PD1_C_3") (pintype "passive"))
    )
    (net (code "32") (name "Net-(U12B-OUT)") (class "Default")
      (node (ref "C43") (pin "2") (pinfunction "2_2") (pintype "passive"))
      (node (ref "U12") (pin "7") (pinfunction "OUT_7") (pintype "output"))
      (node (ref "opto2") (pin "1") (pinfunction "LED_C_1") (pintype "passive"))
    )
    (net (code "33") (name "Net-(U12D-IN-)") (class "Default")
      (node (ref "C49") (pin "1") (pinfunction "1_1") (pintype "passive"))
      (node (ref "R23") (pin "2") (pinfunction "2_2") (pintype "passive"))
      (node (ref "U12") (pin "13") (pinfunction "IN-_13") (pintype "input"))
      (node (ref "opto3") (pin "3") (pinfunction "PD1_C_3") (pintype "passive"))
    )
    (net (code "34") (name "Net-(U12D-OUT)") (class "Default")
      (node (ref "C49") (pin "2") (pinfunction "2_2") (pintype "passive"))
      (node (ref "U12") (pin "14") (pinfunction "OUT_14") (pintype "output"))
      (node (ref "opto3") (pin "1") (pinfunction "LED_C_1") (pintype "passive"))
    )
    (net (code "35") (name "Net-(U13A-IN+)") (class "Default")
      (node (ref "Rx3") (pin "1") (pinfunction "1_1") (pintype "passive"))
      (node (ref "Rx4") (pin "2") (pinfunction "2_2") (pintype "passive"))
      (node (ref "U13") (pin "3") (pinfunction "IN+_3") (pintype "input"))
    )
    (net (code "36") (name "Net-(U13A-IN-)") (class "Default")
      (node (ref "U13") (pin "1") (pinfunction "OUT_1") (pintype "output"))
      (node (ref "U13") (pin "2") (pinfunction "IN-_2") (pintype "input"))
    )
    (net (code "37") (name "Net-(U13B-IN+)") (class "Default")
      (node (ref "Rx1") (pin "1") (pinfunction "1_1") (pintype "passive"))
      (node (ref "Rx2") (pin "2") (pinfunction "2_2") (pintype "passive"))
      (node (ref "U13") (pin "5") (pinfunction "IN+_5") (pintype "input"))
    )
    (net (code "38") (name "Net-(U13B-IN-)") (class "Default")
      (node (ref "U13") (pin "6") (pinfunction "IN-_6") (pintype "input"))
      (node (ref "U13") (pin "7") (pinfunction "OUT_7") (pintype "output"))
    )
    (net (code "39") (name "Net-(U13C-IN+)") (class "Default")
      (node (ref "Rx5") (pin "1") (pinfunction "1_1") (pintype "passive"))
      (node (ref "Rx6") (pin "2") (pinfunction "2_2") (pintype "passive"))
      (node (ref "U13") (pin "10") (pinfunction "IN+_10") (pintype "input"))
    )
    (net (code "40") (name "Net-(U13C-IN-)") (class "Default")
      (node (ref "U13") (pin "8") (pinfunction "OUT_8") (pintype "output"))
      (node (ref "U13") (pin "9") (pinfunction "IN-_9") (pintype "input"))
    )
    (net (code "41") (name "Net-(U13D-IN-)") (class "Default")
      (node (ref "C53") (pin "1") (pinfunction "1_1") (pintype "passive"))
      (node (ref "R26") (pin "1") (pinfunction "1_1") (pintype "passive"))
      (node (ref "U13") (pin "13") (pinfunction "IN-_13") (pintype "input"))
      (node (ref "opto4") (pin "6") (pinfunction "PD2_C_6") (pintype "passive"))
    )
    (net (code "42") (name "Net-(U14A-IN-)") (class "Default")
      (node (ref "U14") (pin "1") (pinfunction "OUT_1") (pintype "output"))
      (node (ref "U14") (pin "2") (pinfunction "IN-_2") (pintype "input"))
    )
    (net (code "43") (name "Net-(U14B-IN-)") (class "Default")
      (node (ref "C54") (pin "1") (pinfunction "1_1") (pintype "passive"))
      (node (ref "R28") (pin "2") (pinfunction "2_2") (pintype "passive"))
      (node (ref "U14") (pin "6") (pinfunction "IN-_6") (pintype "input"))
      (node (ref "opto4") (pin "3") (pinfunction "PD1_C_3") (pintype "passive"))
    )
    (net (code "44") (name "Net-(U14B-OUT)") (class "Default")
      (node (ref "C54") (pin "2") (pinfunction "2_2") (pintype "passive"))
      (node (ref "U14") (pin "7") (pinfunction "OUT_7") (pintype "output"))
      (node (ref "opto4") (pin "1") (pinfunction "LED_C_1") (pintype "passive"))
    )
    (net (code "45") (name "Net-(U14C-OUT)") (class "Default")
      (node (ref "C52") (pin "2") (pinfunction "2_2") (pintype "passive"))
      (node (ref "R27") (pin "1") (pinfunction "1_1") (pintype "passive"))
      (node (ref "R30") (pin "2") (pinfunction "2_2") (pintype "passive"))
      (node (ref "U14") (pin "8") (pinfunction "OUT_8") (pintype "output"))
    )
    (net (code "46") (name "Net-(U14D-IN-)") (class "Default")
      (node (ref "R35") (pin "2") (pinfunction "2_2") (pintype "passive"))
      (node (ref "U14") (pin "13") (pinfunction "IN-_13") (pintype "input"))
      (node (ref "U14") (pin "14") (pinfunction "OUT_14") (pintype "output"))
    )
    (net (code "47") (name "Net-(opto1-LED_A)") (class "Default")
      (node (ref "R19") (pin "2") (pinfunction "2_2") (pintype "passive"))
      (node (ref "opto1") (pin "2") (pinfunction "LED_A_2") (pintype "passive"))
    )
    (net (code "48") (name "Net-(opto2-LED_A)") (class "Default")
      (node (ref "R22") (pin "2") (pinfunction "2_2") (pintype "passive"))
      (node (ref "opto2") (pin "2") (pinfunction "LED_A_2") (pintype "passive"))
    )
    (net (code "49") (name "Net-(opto3-LED_A)") (class "Default")
      (node (ref "R25") (pin "2") (pinfunction "2_2") (pintype "passive"))
      (node (ref "opto3") (pin "2") (pinfunction "LED_A_2") (pintype "passive"))
    )
    (net (code "50") (name "Net-(opto4-LED_A)") (class "Default")
      (node (ref "R29") (pin "2") (pinfunction "2_2") (pintype "passive"))
      (node (ref "opto4") (pin "2") (pinfunction "LED_A_2") (pintype "passive"))
    )
    (net (code "51") (name "Net-(opto5-LED_A)") (class "Default")
      (node (ref "R34") (pin "2") (pinfunction "2_2") (pintype "passive"))
      (node (ref "opto5") (pin "2") (pinfunction "LED_A_2") (pintype "passive"))
    )
    (net (code "52") (name "P-5V") (class "Default")
      (node (ref "C42") (pin "2") (pinfunction "2_2") (pintype "passive"))
      (node (ref "U10") (pin "11") (pinfunction "V-_11") (pintype "power_in"))
    )
    (net (code "53") (name "P5V") (class "Default")
      (node (ref "C39") (pin "2") (pinfunction "2_2") (pintype "passive"))
      (node (ref "R19") (pin "1") (pinfunction "1_1") (pintype "passive"))
      (node (ref "R34") (pin "1") (pinfunction "1_1") (pintype "passive"))
      (node (ref "U10") (pin "4") (pinfunction "V+_4") (pintype "power_in"))
    )
    (net (code "54") (name "S-5V") (class "Default")
      (node (ref "C48") (pin "2") (pinfunction "2_2") (pintype "passive"))
      (node (ref "C60") (pin "2") (pinfunction "2_2") (pintype "passive"))
      (node (ref "U12") (pin "11") (pinfunction "V-_11") (pintype "power_in"))
      (node (ref "U14") (pin "11") (pinfunction "V-_11") (pintype "power_in"))
    )
    (net (code "55") (name "S5V") (class "Default")
      (node (ref "C45") (pin "2") (pinfunction "2_2") (pintype "passive"))
      (node (ref "C55") (pin "2") (pinfunction "2_2") (pintype "passive"))
      (node (ref "R22") (pin "1") (pinfunction "1_1") (pintype "passive"))
      (node (ref "R25") (pin "1") (pinfunction "1_1") (pintype "passive"))
      (node (ref "R29") (pin "1") (pinfunction "1_1") (pintype "passive"))
      (node (ref "U12") (pin "4") (pinfunction "V+_4") (pintype "power_in"))
      (node (ref "U14") (pin "4") (pinfunction "V+_4") (pintype "power_in"))
    )
    (net (code "56") (name "unconnected-(U10B-V+-Pad4)") (class "Default")
      (node (ref "U10") (pin "4") (pinfunction "V+_4") (pintype "power_in"))
    )
    (net (code "57") (name "unconnected-(U10B-V--Pad11)") (class "Default")
      (node (ref "U10") (pin "11") (pinfunction "V-_11") (pintype "power_in"))
    )
    (net (code "58") (name "unconnected-(U10C-V+-Pad4)") (class "Default")
      (node (ref "U10") (pin "4") (pinfunction "V+_4") (pintype "power_in"))
    )
    (net (code "59") (name "unconnected-(U10C-V--Pad11)") (class "Default")
      (node (ref "U10") (pin "11") (pinfunction "V-_11") (pintype "power_in"))
    )
    (net (code "60") (name "unconnected-(U10D-V+-Pad4)") (class "Default")
      (node (ref "U10") (pin "4") (pinfunction "V+_4") (pintype "power_in"))
    )
    (net (code "61") (name "unconnected-(U10D-V--Pad11)") (class "Default")
      (node (ref "U10") (pin "11") (pinfunction "V-_11") (pintype "power_in"))
    )
    (net (code "62") (name "unconnected-(U11A-V+-Pad4)") (class "Default")
      (node (ref "U11") (pin "4") (pinfunction "V+_4") (pintype "power_in"))
    )
    (net (code "63") (name "unconnected-(U11A-V--Pad11)") (class "Default")
      (node (ref "U11") (pin "11") (pinfunction "V-_11") (pintype "power_in"))
    )
    (net (code "64") (name "unconnected-(U11C-V+-Pad4)") (class "Default")
      (node (ref "U11") (pin "4") (pinfunction "V+_4") (pintype "power_in"))
    )
    (net (code "65") (name "unconnected-(U11C-V--Pad11)") (class "Default")
      (node (ref "U11") (pin "11") (pinfunction "V-_11") (pintype "power_in"))
    )
    (net (code "66") (name "unconnected-(U11D-V+-Pad4)") (class "Default")
      (node (ref "U11") (pin "4") (pinfunction "V+_4") (pintype "power_in"))
    )
    (net (code "67") (name "unconnected-(U11D-V--Pad11)") (class "Default")
      (node (ref "U11") (pin "11") (pinfunction "V-_11") (pintype "power_in"))
    )
    (net (code "68") (name "unconnected-(U12B-V+-Pad4)") (class "Default")
      (node (ref "U12") (pin "4") (pinfunction "V+_4") (pintype "power_in"))
    )
    (net (code "69") (name "unconnected-(U12B-V--Pad11)") (class "Default")
      (node (ref "U12") (pin "11") (pinfunction "V-_11") (pintype "power_in"))
    )
    (net (code "70") (name "unconnected-(U12C-V+-Pad4)") (class "Default")
      (node (ref "U12") (pin "4") (pinfunction "V+_4") (pintype "power_in"))
    )
    (net (code "71") (name "unconnected-(U12C-V--Pad11)") (class "Default")
      (node (ref "U12") (pin "11") (pinfunction "V-_11") (pintype "power_in"))
    )
    (net (code "72") (name "unconnected-(U12D-V+-Pad4)") (class "Default")
      (node (ref "U12") (pin "4") (pinfunction "V+_4") (pintype "power_in"))
    )
    (net (code "73") (name "unconnected-(U12D-V--Pad11)") (class "Default")
      (node (ref "U12") (pin "11") (pinfunction "V-_11") (pintype "power_in"))
    )
    (net (code "74") (name "unconnected-(U14A-V+-Pad4)") (class "Default")
      (node (ref "U14") (pin "4") (pinfunction "V+_4") (pintype "power_in"))
    )
    (net (code "75") (name "unconnected-(U14A-V--Pad11)") (class "Default")
      (node (ref "U14") (pin "11") (pinfunction "V-_11") (pintype "power_in"))
    )
    (net (code "76") (name "unconnected-(U14B-V+-Pad4)") (class "Default")
      (node (ref "U14") (pin "4") (pinfunction "V+_4") (pintype "power_in"))
    )
    (net (code "77") (name "unconnected-(U14B-V--Pad11)") (class "Default")
      (node (ref "U14") (pin "11") (pinfunction "V-_11") (pintype "power_in"))
    )
    (net (code "78") (name "unconnected-(U14D-V+-Pad4)") (class "Default")
      (node (ref "U14") (pin "4") (pinfunction "V+_4") (pintype "power_in"))
    )
    (net (code "79") (name "unconnected-(U14D-V--Pad11)") (class "Default")
      (node (ref "U14") (pin "11") (pinfunction "V-_11") (pintype "power_in"))
    )
    (net (code "80") (name "unconnected-(opto1-NC-Pad7)") (class "Default")
      (node (ref "opto1") (pin "7") (pinfunction "NC_7") (pintype "passive"))
    )
    (net (code "81") (name "unconnected-(opto1-NC-Pad8)") (class "Default")
      (node (ref "opto1") (pin "8") (pinfunction "NC_8") (pintype "passive"))
    )
    (net (code "82") (name "unconnected-(opto2-NC-Pad7)") (class "Default")
      (node (ref "opto2") (pin "7") (pinfunction "NC_7") (pintype "passive"))
    )
    (net (code "83") (name "unconnected-(opto2-NC-Pad8)") (class "Default")
      (node (ref "opto2") (pin "8") (pinfunction "NC_8") (pintype "passive"))
    )
    (net (code "84") (name "unconnected-(opto3-NC-Pad7)") (class "Default")
      (node (ref "opto3") (pin "7") (pinfunction "NC_7") (pintype "passive"))
    )
    (net (code "85") (name "unconnected-(opto3-NC-Pad8)") (class "Default")
      (node (ref "opto3") (pin "8") (pinfunction "NC_8") (pintype "passive"))
    )
    (net (code "86") (name "unconnected-(opto4-NC-Pad7)") (class "Default")
      (node (ref "opto4") (pin "7") (pinfunction "NC_7") (pintype "passive"))
    )
    (net (code "87") (name "unconnected-(opto4-NC-Pad8)") (class "Default")
      (node (ref "opto4") (pin "8") (pinfunction "NC_8") (pintype "passive"))
    )
    (net (code "88") (name "unconnected-(opto5-NC-Pad7)") (class "Default")
      (node (ref "opto5") (pin "7") (pinfunction "NC_7") (pintype "passive"))
    )
    (net (code "89") (name "unconnected-(opto5-NC-Pad8)") (class "Default")
      (node (ref "opto5") (pin "8") (pinfunction "NC_8") (pintype "passive"))
    )
  )
)
